# STB_Driver_ISL78171.net
KiCad netlist of a schematic drawn in Altium Designer
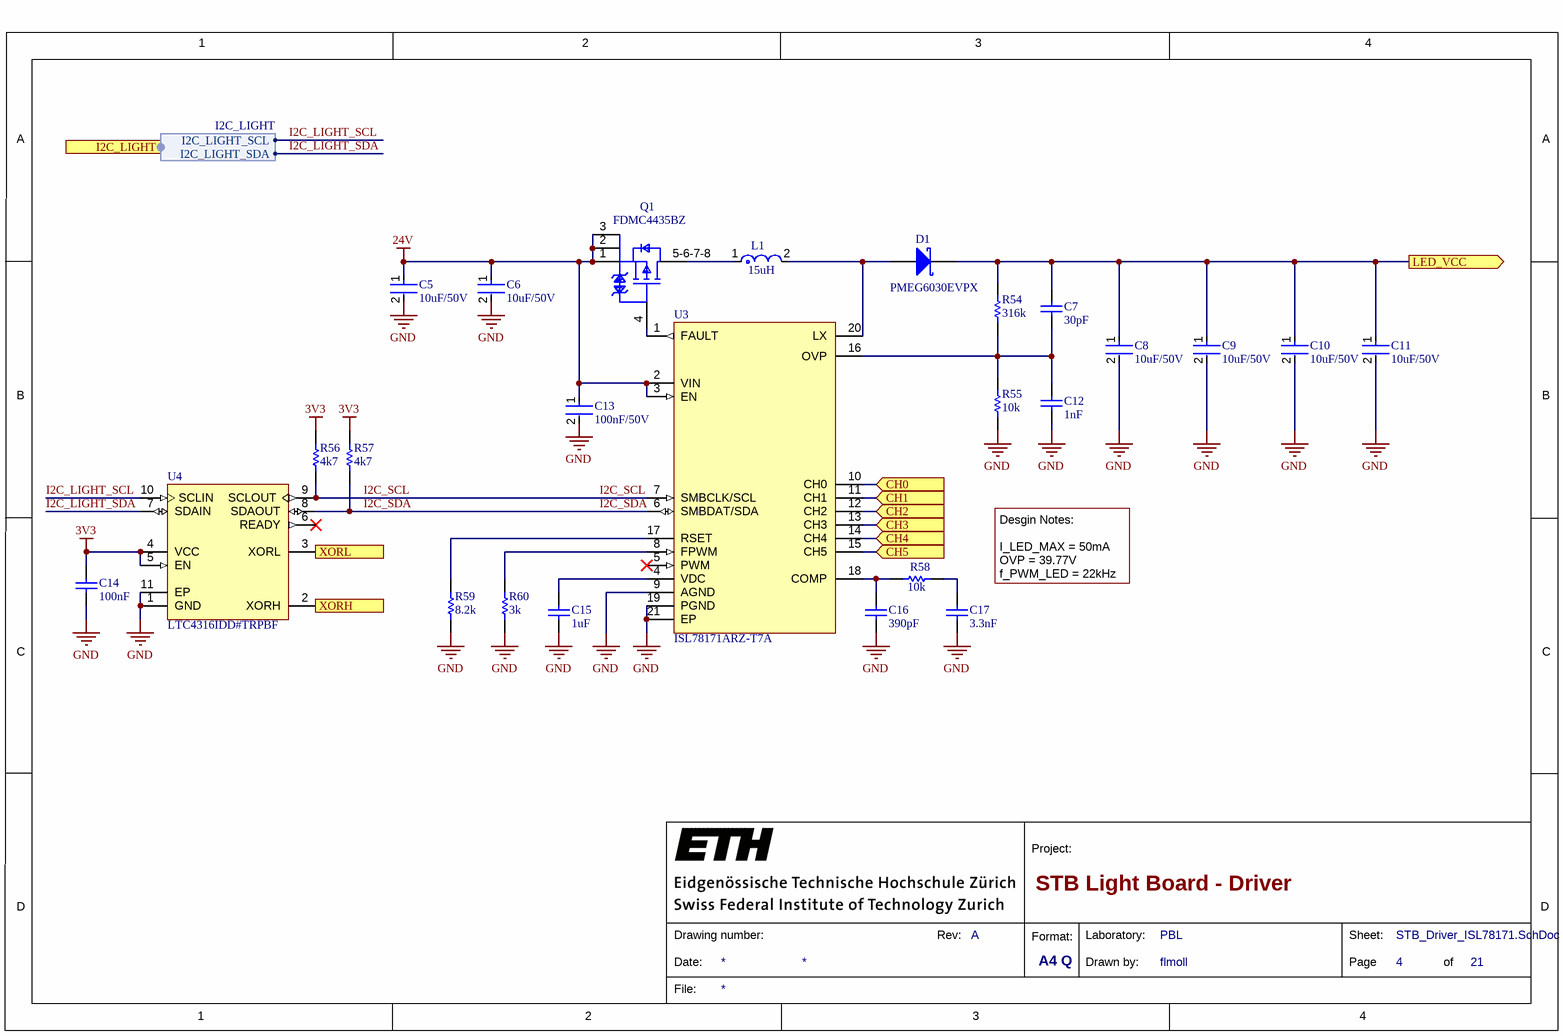
[diagram p0: STB_Driver_ISL78171.SchDoc]

(export (version "E")
  (design (tool "Eeschema 10.0.6"))
  (components
    (comp (ref "C5")
      (value "10uF/50V")
      (footprint "FP-CL31B106KBHNNNE-MFG")
      (description "CAP CER 10UF 50V X7R 1206")
      (fields (field (name "MANUFACTURER") "Samsung") (field (name "TOLERANCE") "10%"))
      (libsource (lib "Altium Content Vault") (part "b4654b650e69147ec39a6b967a45e02"))
    )
    (comp (ref "C6")
      (value "10uF/50V")
      (footprint "FP-CL31B106KBHNNNE-MFG")
      (description "CAP CER 10UF 50V X7R 1206")
      (fields (field (name "MANUFACTURER") "Samsung") (field (name "TOLERANCE") "10%"))
      (libsource (lib "Altium Content Vault") (part "b4654b650e69147ec39a6b967a45e02"))
    )
    (comp (ref "C7")
      (value "30pF")
      (footprint "CAPC1005X56X25LL10T15")
      (fields
        (field (name "PART NUMBER") "04025A300JAT2A")
        (field (name "MANUFACTURER") "AVX Interconnect / Elco")
      )
      (libsource (lib "Altium Content Vault") (part "CAP"))
    )
    (comp (ref "C8")
      (value "10uF/50V")
      (footprint "FP-CL31B106KBHNNNE-MFG")
      (description "CAP CER 10UF 50V X7R 1206")
      (fields (field (name "MANUFACTURER") "Samsung") (field (name "TOLERANCE") "10%"))
      (libsource (lib "Altium Content Vault") (part "b4654b650e69147ec39a6b967a45e02"))
    )
    (comp (ref "C9")
      (value "10uF/50V")
      (footprint "FP-CL31B106KBHNNNE-MFG")
      (description "CAP CER 10UF 50V X7R 1206")
      (fields (field (name "MANUFACTURER") "Samsung") (field (name "TOLERANCE") "10%"))
      (libsource (lib "Altium Content Vault") (part "b4654b650e69147ec39a6b967a45e02"))
    )
    (comp (ref "C10")
      (value "10uF/50V")
      (footprint "FP-CL31B106KBHNNNE-MFG")
      (description "CAP CER 10UF 50V X7R 1206")
      (fields (field (name "MANUFACTURER") "Samsung") (field (name "TOLERANCE") "10%"))
      (libsource (lib "Altium Content Vault") (part "b4654b650e69147ec39a6b967a45e02"))
    )
    (comp (ref "C11")
      (value "10uF/50V")
      (footprint "FP-CL31B106KBHNNNE-MFG")
      (description "CAP CER 10UF 50V X7R 1206")
      (fields (field (name "MANUFACTURER") "Samsung") (field (name "TOLERANCE") "10%"))
      (libsource (lib "Altium Content Vault") (part "b4654b650e69147ec39a6b967a45e02"))
    )
    (comp (ref "C12")
      (value "1nF")
      (footprint "CAPC1005X55X25LL5T10")
      (description "Chip Capacitor, 1 nF, +/- 10%, 50 V, -55 to 125 degC, 0402 (1005 Metric), RoHS, Tape and Reel")
      (fields (field (name "TOLERANCE") "10%") (field (name "MANUFACTURER") "Murata"))
      (libsource (lib "") (part "CAP-NP-2_1"))
    )
    (comp (ref "C13")
      (value "100nF/50V")
      (footprint "FP-CL10-0_1-MFG")
      (description "CAP CER 0.1UF 50V X7R 0603")
      (fields
        (field (name "MANUFACTURER") "Samsung Electro-Mechanics America, Inc")
        (field (name "MANUFACTURER PART NUMBER") "CL10B104JB8NNNC")
      )
      (libsource (lib "Altium Content Vault") (part "b4654b650e69147ec39a6b967a45e02"))
    )
    (comp (ref "C14")
      (value "100nF")
      (footprint "CAPC1050X55X23LL05T13")
      (description "Chip Capacitor, 100 nF, +/- 10%, 16 V, -55 to 125 degC, 0402 (1005 Metric), RoHS, Tape and Reel")
      (fields
        (field (name "MANUFACTURER") "Samsung Electro-Mechanics")
        (field (name "MANUFACTURER PART NUMBER") "CL05B104KO5NNNC")
      )
      (libsource (lib "Altium Content Vault") (part "CAP-NP-2"))
    )
    (comp (ref "C15")
      (value "1uF")
      (footprint "CAPC1608X90X35LL15T15")
      (fields (field (name "MANUFACTURER") "Kemet") (field (name "PART NUMBER") "C0603C105K4RACTU"))
      (libsource (lib "Altium Content Vault") (part "CAP"))
    )
    (comp (ref "C16")
      (value "390pF")
      (footprint "CAPC1005X56X25LL10T15")
      (fields
        (field (name "MANUFACTURER") "AVX Interconnect / Elco")
        (field (name "PART NUMBER") "04025C391JAT2A")
      )
      (libsource (lib "Altium Content Vault") (part "CAP"))
    )
    (comp (ref "C17")
      (value "3.3nF")
      (footprint "CAPC1005X56X25LL10T15")
      (fields
        (field (name "MANUFACTURER") "AVX Interconnect / Elco")
        (field (name "PART NUMBER") "04023C332KAT2A")
      )
      (libsource (lib "Altium Content Vault") (part "CAP"))
    )
    (comp (ref "D1")
      (value "PMEG6030EVPX")
      (footprint "SOD-128")
      (description "Rectifier Diode, Schottky, 1 Phase, 1 Element, 4.2A, 60V V(RRM), Silicon")
      (fields (field (name "MANUFACTURER") "Nexperia"))
      (libsource (lib "ETHZ Vault") (part "Diode Schottky"))
    )
    (comp (ref "L1")
      (value "15uH")
      (footprint "FP-XAL6060-MFG")
      (description "Power inductor, shielded, 20% tol, SMT, RoHS, halogen, SMD2")
      (fields (field (name "TOLERANCE") "20%") (field (name "MANUFACTURER") "Coilcraft"))
      (libsource (lib "Altium Content Vault") (part "4cc4b267dca4c8e51f7102f422741d8"))
    )
    (comp (ref "Q1")
      (value "FDMC4435BZ")
      (footprint "FP-511DQ-MFG")
      (description "MOSFET P-CH 30V 8.5A POWER33")
      (fields
        (field (name "MANUFACTURER") "ON Semiconductor")
        (field (name "OCTOPART") "https://octopart.com/fdmc4435bz-on+semiconductor-84326033")
      )
      (libsource (lib "Altium Content Vault") (part "22361b50670c932331d08dd85748805"))
    )
    (comp (ref "R54")
      (value "316k")
      (footprint "RESC1005X40X25LL05T05")
      (fields
        (field (name "MANUFACTURER") "Panasonic")
        (field (name "PART NUMBER") "ERJ-2RKF3163X")
        (field (name "TOLERANCE") "1%")
      )
      (libsource (lib "Altium Content Vault") (part "RES"))
    )
    (comp (ref "R55")
      (value "10k")
      (footprint "RESC1005X40X25LL05T05")
      (description "Chip Resistor, 10 KOhm, +/- 1%, 0.1 W, -55 to 155 degC, 0402 (1005 Metric), RoHS, Tape and Reel")
      (fields (field (name "TOLERANCE") "1%") (field (name "MANUFACTURER") "Panasonic"))
      (libsource (lib "Altium Content Vault") (part "RES-2"))
    )
    (comp (ref "R56")
      (value "4k7")
      (footprint "RESC1005X40X25LL05T10")
      (fields
        (field (name "MANUFACTURER") "Yageo / Phycomp")
        (field (name "PART NUMBER") "RC0402FR-074K7L")
        (field (name "TOLERANCE") "1%")
      )
      (libsource (lib "Altium Content Vault") (part "RES"))
    )
    (comp (ref "R57")
      (value "4k7")
      (footprint "RESC1005X40X25LL05T10")
      (fields
        (field (name "MANUFACTURER") "Yageo / Phycomp")
        (field (name "PART NUMBER") "RC0402FR-074K7L")
        (field (name "TOLERANCE") "1%")
      )
      (libsource (lib "Altium Content Vault") (part "RES"))
    )
    (comp (ref "R58")
      (value "10k")
      (footprint "RESC1005X40X25LL05T05")
      (description "Chip Resistor, 10 KOhm, +/- 1%, 0.1 W, -55 to 155 degC, 0402 (1005 Metric), RoHS, Tape and Reel")
      (fields (field (name "TOLERANCE") "1%") (field (name "MANUFACTURER") "Panasonic"))
      (libsource (lib "Altium Content Vault") (part "RES-2"))
    )
    (comp (ref "R59")
      (value "8.2k")
      (footprint "RESC1005X40X25LL05T05")
      (fields
        (field (name "PART NUMBER") "CRCW04028K20FKED")
        (field (name "MANUFACTURER") "Vishay Dale")
        (field (name "TOLERANCE") "1%")
      )
      (libsource (lib "Altium Content Vault") (part "RES"))
    )
    (comp (ref "R60")
      (value "3k")
      (footprint "RESC1005X40X25LL05T10")
      (fields
        (field (name "PART NUMBER") "RC0402FR-073KL")
        (field (name "MANUFACTURER") "Yageo / Phycomp")
        (field (name "TOLERANCE") "1%")
      )
      (libsource (lib "Altium Content Vault") (part "RES"))
    )
    (comp (ref "U3")
      (value "ISL78171ARZ-T7A")
      (footprint "LT-UDC-20_N")
      (description "LED Driver IC 6 Output DC DC Regulator Step-Up (Boost) Analog, I²C, PWM Dimming 50mA 20-QFN (3x4)")
      (fields (field (name "MANUFACTURER") "Renesas"))
      (libsource (lib "ETHZ Vault") (part "ISL78171ARZ-T7A"))
    )
    (comp (ref "U4")
      (value "LTC4316IDD#TRPBF")
      (footprint "DFN10(3x3)_N")
      (description "Single I2C/SMBus Address Translator")
      (fields (field (name "MANUFACTURER") "Analog Devices / Linear Technology"))
      (libsource (lib "ETHZ Vault") (part "LTC4316IDD#TRPBF"))
    )
  )
  (nets
    (net (code "2") (name "/CH0") (class "Default")
      (node (ref "U3") (pin "10") (pinfunction "CH0_10") (pintype "passive"))
    )
    (net (code "3") (name "/CH1") (class "Default")
      (node (ref "U3") (pin "11") (pinfunction "CH1_11") (pintype "passive"))
    )
    (net (code "4") (name "/CH2") (class "Default")
      (node (ref "U3") (pin "12") (pinfunction "CH2_12") (pintype "passive"))
    )
    (net (code "5") (name "/CH3") (class "Default")
      (node (ref "U3") (pin "13") (pinfunction "CH3_13") (pintype "passive"))
    )
    (net (code "6") (name "/CH4") (class "Default")
      (node (ref "U3") (pin "14") (pinfunction "CH4_14") (pintype "passive"))
    )
    (net (code "7") (name "/CH5") (class "Default")
      (node (ref "U3") (pin "15") (pinfunction "CH5_15") (pintype "passive"))
    )
    (net (code "8") (name "/I2C_LIGHT_SCL") (class "Default")
      (node (ref "U4") (pin "10") (pinfunction "SCLIN_10") (pintype "input"))
    )
    (net (code "9") (name "/I2C_LIGHT_SDA") (class "Default")
      (node (ref "U4") (pin "7") (pinfunction "SDAIN_7") (pintype "bidirectional"))
    )
    (net (code "10") (name "/I2C_SCL") (class "Default")
      (node (ref "R56") (pin "1") (pinfunction "1_1") (pintype "passive"))
      (node (ref "U3") (pin "7") (pinfunction "SMBCLK/SCL_7") (pintype "input"))
      (node (ref "U4") (pin "9") (pinfunction "SCLOUT_9") (pintype "output"))
    )
    (net (code "11") (name "/I2C_SDA") (class "Default")
      (node (ref "R57") (pin "1") (pinfunction "1_1") (pintype "passive"))
      (node (ref "U3") (pin "6") (pinfunction "SMBDAT/SDA_6") (pintype "bidirectional"))
      (node (ref "U4") (pin "8") (pinfunction "SDAOUT_8") (pintype "bidirectional"))
    )
    (net (code "12") (name "/LED_VCC") (class "Default")
      (node (ref "C10") (pin "1") (pinfunction "1_1") (pintype "passive"))
      (node (ref "C11") (pin "1") (pinfunction "1_1") (pintype "passive"))
      (node (ref "C7") (pin "2") (pinfunction "2_2") (pintype "passive"))
      (node (ref "C8") (pin "1") (pinfunction "1_1") (pintype "passive"))
      (node (ref "C9") (pin "1") (pinfunction "1_1") (pintype "passive"))
      (node (ref "D1") (pin "1") (pinfunction "K_1") (pintype "passive"))
      (node (ref "R54") (pin "2") (pinfunction "2_2") (pintype "passive"))
    )
    (net (code "13") (name "/XORH") (class "Default")
      (node (ref "U4") (pin "2") (pinfunction "XORH_2") (pintype "passive"))
    )
    (net (code "14") (name "/XORL") (class "Default")
      (node (ref "U4") (pin "3") (pinfunction "XORL_3") (pintype "passive"))
    )
    (net (code "16") (name "3V3") (class "Default")
      (node (ref "C14") (pin "2") (pinfunction "2_2") (pintype "passive"))
      (node (ref "R56") (pin "2") (pinfunction "2_2") (pintype "passive"))
      (node (ref "R57") (pin "2") (pinfunction "2_2") (pintype "passive"))
      (node (ref "U4") (pin "4") (pinfunction "VCC_4") (pintype "power_in"))
      (node (ref "U4") (pin "5") (pinfunction "EN_5") (pintype "input"))
    )
    (net (code "17") (name "24V") (class "Default")
      (node (ref "C13") (pin "1") (pinfunction "1_1") (pintype "passive"))
      (node (ref "C5") (pin "1") (pinfunction "1_1") (pintype "passive"))
      (node (ref "C6") (pin "1") (pinfunction "1_1") (pintype "passive"))
      (node (ref "Q1") (pin "1") (pinfunction "S_1") (pintype "passive"))
      (node (ref "Q1") (pin "2") (pinfunction "S_2") (pintype "passive"))
      (node (ref "Q1") (pin "3") (pinfunction "S_3") (pintype "passive"))
      (node (ref "U3") (pin "2") (pinfunction "VIN_2") (pintype "power_in"))
      (node (ref "U3") (pin "3") (pinfunction "EN_3") (pintype "input"))
    )
    (net (code "18") (name "GND") (class "Default")
      (node (ref "C10") (pin "2") (pinfunction "2_2") (pintype "passive"))
      (node (ref "C11") (pin "2") (pinfunction "2_2") (pintype "passive"))
      (node (ref "C12") (pin "1") (pinfunction "1_1") (pintype "passive"))
      (node (ref "C13") (pin "2") (pinfunction "2_2") (pintype "passive"))
      (node (ref "C14") (pin "1") (pinfunction "1_1") (pintype "passive"))
      (node (ref "C15") (pin "1") (pinfunction "1_1") (pintype "passive"))
      (node (ref "C16") (pin "1") (pinfunction "1_1") (pintype "passive"))
      (node (ref "C17") (pin "1") (pinfunction "1_1") (pintype "passive"))
      (node (ref "C5") (pin "2") (pinfunction "2_2") (pintype "passive"))
      (node (ref "C6") (pin "2") (pinfunction "2_2") (pintype "passive"))
      (node (ref "C8") (pin "2") (pinfunction "2_2") (pintype "passive"))
      (node (ref "C9") (pin "2") (pinfunction "2_2") (pintype "passive"))
      (node (ref "R55") (pin "2") (pinfunction "2_2") (pintype "passive"))
      (node (ref "R59") (pin "1") (pinfunction "1_1") (pintype "passive"))
      (node (ref "R60") (pin "1") (pinfunction "1_1") (pintype "passive"))
      (node (ref "U3") (pin "19") (pinfunction "PGND_19") (pintype "power_in"))
      (node (ref "U3") (pin "21") (pinfunction "EP_21") (pintype "power_in"))
      (node (ref "U3") (pin "9") (pinfunction "AGND_9") (pintype "power_in"))
      (node (ref "U4") (pin "1") (pinfunction "GND_1") (pintype "power_in"))
      (node (ref "U4") (pin "11") (pinfunction "EP_11") (pintype "power_in"))
    )
    (net (code "19") (name "Net-(C17-Pad2)") (class "Default")
      (node (ref "C17") (pin "2") (pinfunction "2_2") (pintype "passive"))
      (node (ref "R58") (pin "1") (pinfunction "1_1") (pintype "passive"))
    )
    (net (code "20") (name "Net-(D1-A)") (class "Default")
      (node (ref "D1") (pin "2") (pinfunction "A_2") (pintype "passive"))
      (node (ref "L1") (pin "2") (pinfunction "2_2") (pintype "passive"))
      (node (ref "U3") (pin "20") (pinfunction "LX_20") (pintype "power_in"))
    )
    (net (code "21") (name "Net-(Q1-D)") (class "Default")
      (node (ref "L1") (pin "1") (pinfunction "1_1") (pintype "passive"))
      (node (ref "Q1") (pin "5-6-7-8") (pinfunction "D_5-6-7-8") (pintype "passive"))
    )
    (net (code "22") (name "Net-(Q1-G)") (class "Default")
      (node (ref "Q1") (pin "4") (pinfunction "G_4") (pintype "passive"))
      (node (ref "U3") (pin "1") (pinfunction "FAULT_1") (pintype "output"))
    )
    (net (code "23") (name "Net-(U3-COMP)") (class "Default")
      (node (ref "C16") (pin "2") (pinfunction "2_2") (pintype "passive"))
      (node (ref "R58") (pin "2") (pinfunction "2_2") (pintype "passive"))
      (node (ref "U3") (pin "18") (pinfunction "COMP_18") (pintype "passive"))
    )
    (net (code "24") (name "Net-(U3-FPWM)") (class "Default")
      (node (ref "R60") (pin "2") (pinfunction "2_2") (pintype "passive"))
      (node (ref "U3") (pin "8") (pinfunction "FPWM_8") (pintype "input"))
    )
    (net (code "25") (name "Net-(U3-OVP)") (class "Default")
      (node (ref "C12") (pin "2") (pinfunction "2_2") (pintype "passive"))
      (node (ref "C7") (pin "1") (pinfunction "1_1") (pintype "passive"))
      (node (ref "R54") (pin "1") (pinfunction "1_1") (pintype "passive"))
      (node (ref "R55") (pin "1") (pinfunction "1_1") (pintype "passive"))
      (node (ref "U3") (pin "16") (pinfunction "OVP_16") (pintype "passive"))
    )
    (net (code "26") (name "Net-(U3-RSET)") (class "Default")
      (node (ref "R59") (pin "2") (pinfunction "2_2") (pintype "passive"))
      (node (ref "U3") (pin "17") (pinfunction "RSET_17") (pintype "passive"))
    )
    (net (code "27") (name "Net-(U3-VDC)") (class "Default")
      (node (ref "C15") (pin "2") (pinfunction "2_2") (pintype "passive"))
      (node (ref "U3") (pin "4") (pinfunction "VDC_4") (pintype "power_in"))
    )
    (net (code "28") (name "unconnected-(U3-PWM-Pad5)") (class "Default")
      (node (ref "U3") (pin "5") (pinfunction "PWM_5") (pintype "input+no_connect"))
    )
    (net (code "29") (name "unconnected-(U4-READY-Pad6)") (class "Default")
      (node (ref "U4") (pin "6") (pinfunction "READY_6") (pintype "output+no_connect"))
    )
  )
)
